# demo-project.net
KiCad netlist of a schematic drawn in EasyEDA
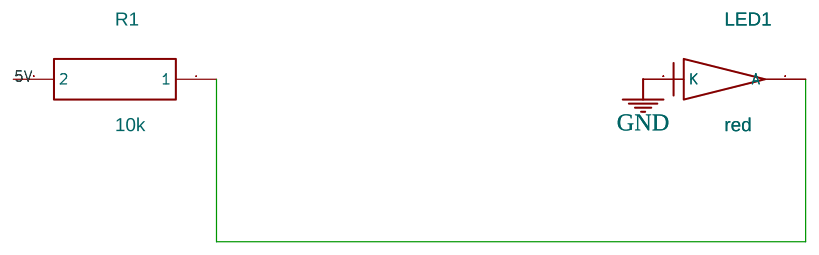
[diagram p0: schematic sheet]

(export (version "E")
  (design (tool "Eeschema 10.0.6"))
  (components
    (comp (ref "LED1") (value "red") (libsource (lib "") (part "led")))
    (comp (ref "R1") (value "10k") (libsource (lib "") (part "resistor")))
  )
  (nets
    (net (code "1") (name "/5V") (class "Default")
      (node (ref "R1") (pin "2") (pinfunction "2_2") (pintype "unspecified"))
    )
    (net (code "2") (name "GND") (class "Default")
      (node (ref "LED1") (pin "2") (pinfunction "K_2") (pintype "unspecified"))
    )
    (net (code "3") (name "Net-(LED1-A)") (class "Default")
      (node (ref "LED1") (pin "1") (pinfunction "A_1") (pintype "unspecified"))
      (node (ref "R1") (pin "1") (pinfunction "1_1") (pintype "unspecified"))
    )
  )
)
